# MT8365_DDR4X.net
KiCad netlist of a schematic drawn in Altium Designer
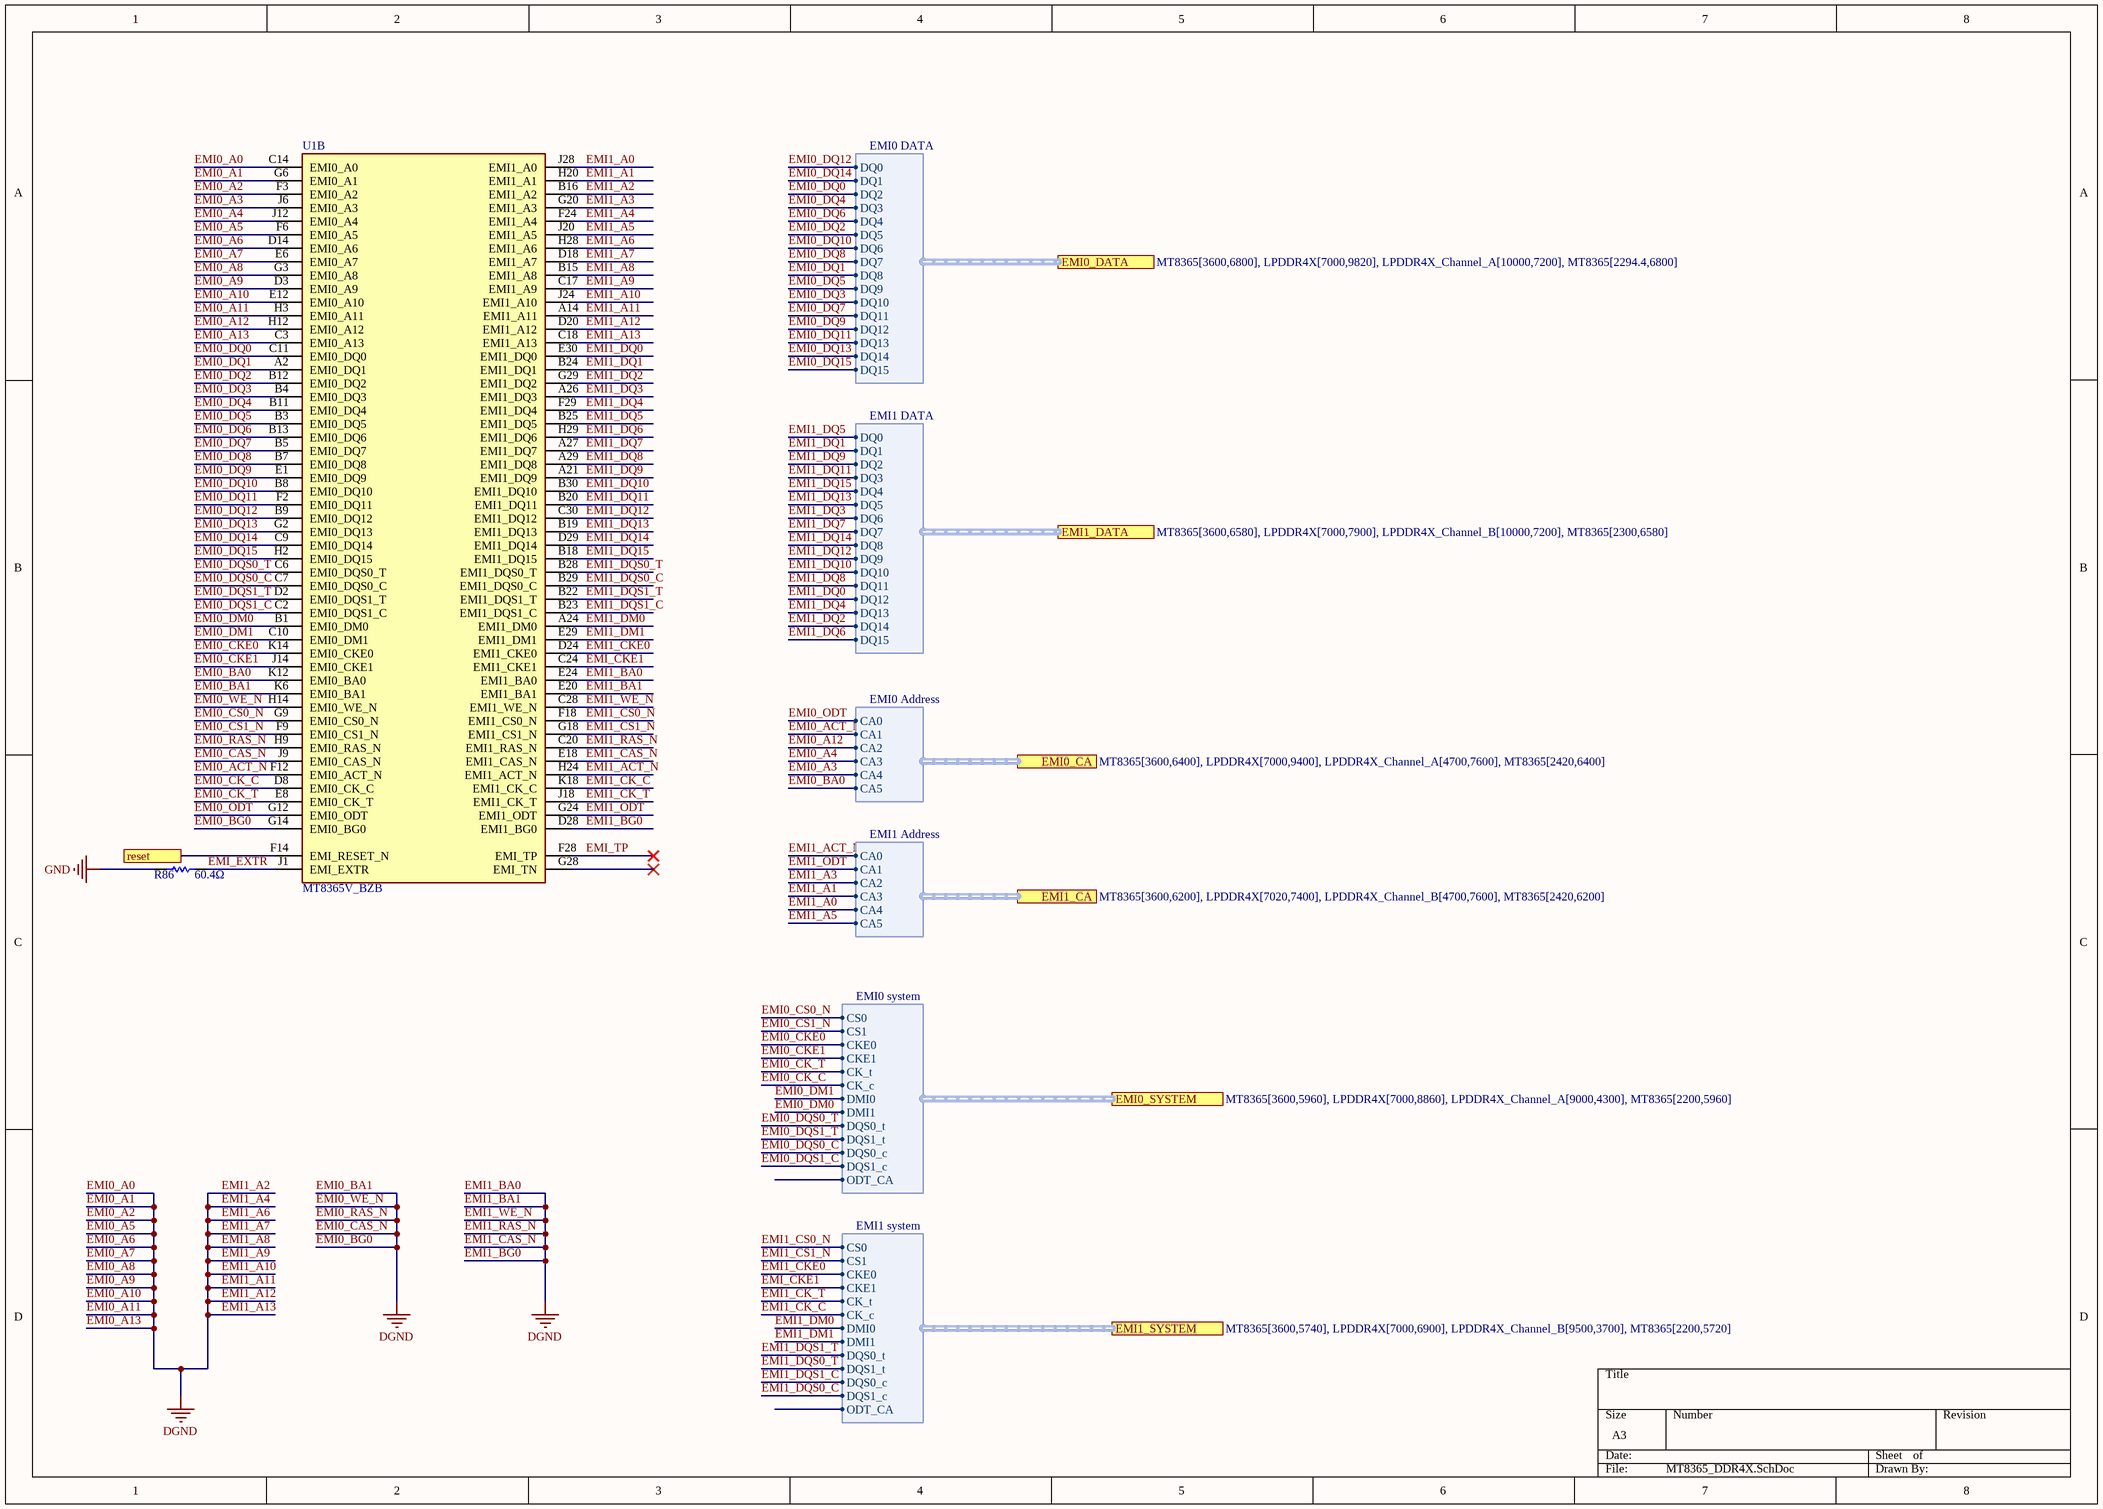
[diagram p0: MT8365_DDR4X.SchDoc]

(export (version "E")
  (design (tool "Eeschema 10.0.6"))
  (components
    (comp (ref "R86")
      (value "60.4Ω")
      (description "Resistor")
      (libsource (lib "Simulation Generic Components") (part "Resistor"))
    )
    (comp (ref "U1")
      (value "MT8365V_BZB")
      (footprint "BGA633C40P30X29_1220X1180X90")
      (description "Integrated Circuit")
      (fields
        (field (name "MANUFACTURER_PART_NUMBER") "MT8365V/BZB")
        (field (name "MOUSER PART NUMBER") "840-MT8365V/BZB")
      )
      (libsource (lib "kit") (part "MT8365V_BZB"))
    )
  )
  (nets
    (net (code "6") (name "/EMI0_A3") (class "Default")
      (node (ref "U1") (pin "J6") (pinfunction "EMI0_A3_J6") (pintype "passive"))
    )
    (net (code "7") (name "/EMI0_A4") (class "Default")
      (node (ref "U1") (pin "J12") (pinfunction "EMI0_A4_J12") (pintype "passive"))
    )
    (net (code "8") (name "/EMI0_A12") (class "Default")
      (node (ref "U1") (pin "H12") (pinfunction "EMI0_A12_H12") (pintype "passive"))
    )
    (net (code "9") (name "/EMI0_ACT_N") (class "Default")
      (node (ref "U1") (pin "F12") (pinfunction "EMI0_ACT_N_F12") (pintype "passive"))
    )
    (net (code "10") (name "/EMI0_BA0") (class "Default")
      (node (ref "U1") (pin "K12") (pinfunction "EMI0_BA0_K12") (pintype "passive"))
    )
    (net (code "11") (name "/EMI0_CKE0") (class "Default")
      (node (ref "U1") (pin "K14") (pinfunction "EMI0_CKE0_K14") (pintype "passive"))
    )
    (net (code "12") (name "/EMI0_CKE1") (class "Default")
      (node (ref "U1") (pin "J14") (pinfunction "EMI0_CKE1_J14") (pintype "passive"))
    )
    (net (code "13") (name "/EMI0_CK_C") (class "Default")
      (node (ref "U1") (pin "D8") (pinfunction "EMI0_CK_C_D8") (pintype "passive"))
    )
    (net (code "14") (name "/EMI0_CK_T") (class "Default")
      (node (ref "U1") (pin "E8") (pinfunction "EMI0_CK_T_E8") (pintype "passive"))
    )
    (net (code "15") (name "/EMI0_CS0_N") (class "Default")
      (node (ref "U1") (pin "G9") (pinfunction "EMI0_CS0_N_G9") (pintype "passive"))
    )
    (net (code "16") (name "/EMI0_CS1_N") (class "Default")
      (node (ref "U1") (pin "F9") (pinfunction "EMI0_CS1_N_F9") (pintype "passive"))
    )
    (net (code "17") (name "/EMI0_DM0") (class "Default")
      (node (ref "U1") (pin "B1") (pinfunction "EMI0_DM0_B1") (pintype "passive"))
    )
    (net (code "18") (name "/EMI0_DM1") (class "Default")
      (node (ref "U1") (pin "C10") (pinfunction "EMI0_DM1_C10") (pintype "passive"))
    )
    (net (code "19") (name "/EMI0_DQ0") (class "Default")
      (node (ref "U1") (pin "C11") (pinfunction "EMI0_DQ0_C11") (pintype "passive"))
    )
    (net (code "20") (name "/EMI0_DQ1") (class "Default")
      (node (ref "U1") (pin "A2") (pinfunction "EMI0_DQ1_A2") (pintype "passive"))
    )
    (net (code "21") (name "/EMI0_DQ2") (class "Default")
      (node (ref "U1") (pin "B12") (pinfunction "EMI0_DQ2_B12") (pintype "passive"))
    )
    (net (code "22") (name "/EMI0_DQ3") (class "Default")
      (node (ref "U1") (pin "B4") (pinfunction "EMI0_DQ3_B4") (pintype "passive"))
    )
    (net (code "23") (name "/EMI0_DQ4") (class "Default")
      (node (ref "U1") (pin "B11") (pinfunction "EMI0_DQ4_B11") (pintype "passive"))
    )
    (net (code "24") (name "/EMI0_DQ5") (class "Default")
      (node (ref "U1") (pin "B3") (pinfunction "EMI0_DQ5_B3") (pintype "passive"))
    )
    (net (code "25") (name "/EMI0_DQ6") (class "Default")
      (node (ref "U1") (pin "B13") (pinfunction "EMI0_DQ6_B13") (pintype "passive"))
    )
    (net (code "26") (name "/EMI0_DQ7") (class "Default")
      (node (ref "U1") (pin "B5") (pinfunction "EMI0_DQ7_B5") (pintype "passive"))
    )
    (net (code "27") (name "/EMI0_DQ8") (class "Default")
      (node (ref "U1") (pin "B7") (pinfunction "EMI0_DQ8_B7") (pintype "passive"))
    )
    (net (code "28") (name "/EMI0_DQ9") (class "Default")
      (node (ref "U1") (pin "E1") (pinfunction "EMI0_DQ9_E1") (pintype "passive"))
    )
    (net (code "29") (name "/EMI0_DQ10") (class "Default")
      (node (ref "U1") (pin "B8") (pinfunction "EMI0_DQ10_B8") (pintype "passive"))
    )
    (net (code "30") (name "/EMI0_DQ11") (class "Default")
      (node (ref "U1") (pin "F2") (pinfunction "EMI0_DQ11_F2") (pintype "passive"))
    )
    (net (code "31") (name "/EMI0_DQ12") (class "Default")
      (node (ref "U1") (pin "B9") (pinfunction "EMI0_DQ12_B9") (pintype "passive"))
    )
    (net (code "32") (name "/EMI0_DQ13") (class "Default")
      (node (ref "U1") (pin "G2") (pinfunction "EMI0_DQ13_G2") (pintype "passive"))
    )
    (net (code "33") (name "/EMI0_DQ14") (class "Default")
      (node (ref "U1") (pin "C9") (pinfunction "EMI0_DQ14_C9") (pintype "passive"))
    )
    (net (code "34") (name "/EMI0_DQ15") (class "Default")
      (node (ref "U1") (pin "H2") (pinfunction "EMI0_DQ15_H2") (pintype "passive"))
    )
    (net (code "35") (name "/EMI0_DQS0_C") (class "Default")
      (node (ref "U1") (pin "C7") (pinfunction "EMI0_DQS0_C_C7") (pintype "passive"))
    )
    (net (code "36") (name "/EMI0_DQS0_T") (class "Default")
      (node (ref "U1") (pin "C6") (pinfunction "EMI0_DQS0_T_C6") (pintype "passive"))
    )
    (net (code "37") (name "/EMI0_DQS1_C") (class "Default")
      (node (ref "U1") (pin "C2") (pinfunction "EMI0_DQS1_C_C2") (pintype "passive"))
    )
    (net (code "38") (name "/EMI0_DQS1_T") (class "Default")
      (node (ref "U1") (pin "D2") (pinfunction "EMI0_DQS1_T_D2") (pintype "passive"))
    )
    (net (code "39") (name "/EMI0_ODT") (class "Default")
      (node (ref "U1") (pin "G12") (pinfunction "EMI0_ODT_G12") (pintype "passive"))
    )
    (net (code "40") (name "/EMI1_A0") (class "Default")
      (node (ref "U1") (pin "J28") (pinfunction "EMI1_A0_J28") (pintype "passive"))
    )
    (net (code "41") (name "/EMI1_A1") (class "Default")
      (node (ref "U1") (pin "H20") (pinfunction "EMI1_A1_H20") (pintype "passive"))
    )
    (net (code "42") (name "/EMI1_A3") (class "Default")
      (node (ref "U1") (pin "G20") (pinfunction "EMI1_A3_G20") (pintype "passive"))
    )
    (net (code "43") (name "/EMI1_A5") (class "Default")
      (node (ref "U1") (pin "J20") (pinfunction "EMI1_A5_J20") (pintype "passive"))
    )
    (net (code "44") (name "/EMI1_ACT_N") (class "Default")
      (node (ref "U1") (pin "H24") (pinfunction "EMI1_ACT_N_H24") (pintype "passive"))
    )
    (net (code "45") (name "/EMI1_CKE0") (class "Default")
      (node (ref "U1") (pin "D24") (pinfunction "EMI1_CKE0_D24") (pintype "passive"))
    )
    (net (code "46") (name "/EMI1_CK_C") (class "Default")
      (node (ref "U1") (pin "K18") (pinfunction "EMI1_CK_C_K18") (pintype "passive"))
    )
    (net (code "47") (name "/EMI1_CK_T") (class "Default")
      (node (ref "U1") (pin "J18") (pinfunction "EMI1_CK_T_J18") (pintype "passive"))
    )
    (net (code "48") (name "/EMI1_CS0_N") (class "Default")
      (node (ref "U1") (pin "F18") (pinfunction "EMI1_CS0_N_F18") (pintype "passive"))
    )
    (net (code "49") (name "/EMI1_CS1_N") (class "Default")
      (node (ref "U1") (pin "G18") (pinfunction "EMI1_CS1_N_G18") (pintype "passive"))
    )
    (net (code "50") (name "/EMI1_DM0") (class "Default")
      (node (ref "U1") (pin "A24") (pinfunction "EMI1_DM0_A24") (pintype "passive"))
    )
    (net (code "51") (name "/EMI1_DM1") (class "Default")
      (node (ref "U1") (pin "E29") (pinfunction "EMI1_DM1_E29") (pintype "passive"))
    )
    (net (code "52") (name "/EMI1_DQ0") (class "Default")
      (node (ref "U1") (pin "E30") (pinfunction "EMI1_DQ0_E30") (pintype "passive"))
    )
    (net (code "53") (name "/EMI1_DQ1") (class "Default")
      (node (ref "U1") (pin "B24") (pinfunction "EMI1_DQ1_B24") (pintype "passive"))
    )
    (net (code "54") (name "/EMI1_DQ2") (class "Default")
      (node (ref "U1") (pin "G29") (pinfunction "EMI1_DQ2_G29") (pintype "passive"))
    )
    (net (code "55") (name "/EMI1_DQ3") (class "Default")
      (node (ref "U1") (pin "A26") (pinfunction "EMI1_DQ3_A26") (pintype "passive"))
    )
    (net (code "56") (name "/EMI1_DQ4") (class "Default")
      (node (ref "U1") (pin "F29") (pinfunction "EMI1_DQ4_F29") (pintype "passive"))
    )
    (net (code "57") (name "/EMI1_DQ5") (class "Default")
      (node (ref "U1") (pin "B25") (pinfunction "EMI1_DQ5_B25") (pintype "passive"))
    )
    (net (code "58") (name "/EMI1_DQ6") (class "Default")
      (node (ref "U1") (pin "H29") (pinfunction "EMI1_DQ6_H29") (pintype "passive"))
    )
    (net (code "59") (name "/EMI1_DQ7") (class "Default")
      (node (ref "U1") (pin "A27") (pinfunction "EMI1_DQ7_A27") (pintype "passive"))
    )
    (net (code "60") (name "/EMI1_DQ8") (class "Default")
      (node (ref "U1") (pin "A29") (pinfunction "EMI1_DQ8_A29") (pintype "passive"))
    )
    (net (code "61") (name "/EMI1_DQ9") (class "Default")
      (node (ref "U1") (pin "A21") (pinfunction "EMI1_DQ9_A21") (pintype "passive"))
    )
    (net (code "62") (name "/EMI1_DQ10") (class "Default")
      (node (ref "U1") (pin "B30") (pinfunction "EMI1_DQ10_B30") (pintype "passive"))
    )
    (net (code "63") (name "/EMI1_DQ11") (class "Default")
      (node (ref "U1") (pin "B20") (pinfunction "EMI1_DQ11_B20") (pintype "passive"))
    )
    (net (code "64") (name "/EMI1_DQ12") (class "Default")
      (node (ref "U1") (pin "C30") (pinfunction "EMI1_DQ12_C30") (pintype "passive"))
    )
    (net (code "65") (name "/EMI1_DQ13") (class "Default")
      (node (ref "U1") (pin "B19") (pinfunction "EMI1_DQ13_B19") (pintype "passive"))
    )
    (net (code "66") (name "/EMI1_DQ14") (class "Default")
      (node (ref "U1") (pin "D29") (pinfunction "EMI1_DQ14_D29") (pintype "passive"))
    )
    (net (code "67") (name "/EMI1_DQ15") (class "Default")
      (node (ref "U1") (pin "B18") (pinfunction "EMI1_DQ15_B18") (pintype "passive"))
    )
    (net (code "68") (name "/EMI1_DQS0_C") (class "Default")
      (node (ref "U1") (pin "B29") (pinfunction "EMI1_DQS0_C_B29") (pintype "passive"))
    )
    (net (code "69") (name "/EMI1_DQS0_T") (class "Default")
      (node (ref "U1") (pin "B28") (pinfunction "EMI1_DQS0_T_B28") (pintype "passive"))
    )
    (net (code "70") (name "/EMI1_DQS1_C") (class "Default")
      (node (ref "U1") (pin "B23") (pinfunction "EMI1_DQS1_C_B23") (pintype "passive"))
    )
    (net (code "71") (name "/EMI1_DQS1_T") (class "Default")
      (node (ref "U1") (pin "B22") (pinfunction "EMI1_DQS1_T_B22") (pintype "passive"))
    )
    (net (code "72") (name "/EMI1_ODT") (class "Default")
      (node (ref "U1") (pin "G24") (pinfunction "EMI1_ODT_G24") (pintype "passive"))
    )
    (net (code "73") (name "/EMI_CKE1") (class "Default")
      (node (ref "U1") (pin "C24") (pinfunction "EMI1_CKE1_C24") (pintype "passive"))
    )
    (net (code "74") (name "/EMI_EXTR") (class "Default")
      (node (ref "R86") (pin "2") (pinfunction "2_2") (pintype "passive"))
      (node (ref "U1") (pin "J1") (pinfunction "EMI_EXTR_J1") (pintype "passive"))
    )
    (net (code "75") (name "/EMI_TP") (class "Default")
      (node (ref "U1") (pin "F28") (pinfunction "EMI_TP_F28") (pintype "passive+no_connect"))
    )
    (net (code "76") (name "/reset") (class "Default")
      (node (ref "U1") (pin "F14") (pinfunction "EMI_RESET_N_F14") (pintype "passive"))
    )
    (net (code "83") (name "DGND") (class "Default")
      (node (ref "U1") (pin "A14") (pinfunction "EMI1_A11_A14") (pintype "passive"))
      (node (ref "U1") (pin "B15") (pinfunction "EMI1_A8_B15") (pintype "passive"))
      (node (ref "U1") (pin "B16") (pinfunction "EMI1_A2_B16") (pintype "passive"))
      (node (ref "U1") (pin "C14") (pinfunction "EMI0_A0_C14") (pintype "passive"))
      (node (ref "U1") (pin "C17") (pinfunction "EMI1_A9_C17") (pintype "passive"))
      (node (ref "U1") (pin "C18") (pinfunction "EMI1_A13_C18") (pintype "passive"))
      (node (ref "U1") (pin "C20") (pinfunction "EMI1_RAS_N_C20") (pintype "passive"))
      (node (ref "U1") (pin "C28") (pinfunction "EMI1_WE_N_C28") (pintype "passive"))
      (node (ref "U1") (pin "C3") (pinfunction "EMI0_A13_C3") (pintype "passive"))
      (node (ref "U1") (pin "D14") (pinfunction "EMI0_A6_D14") (pintype "passive"))
      (node (ref "U1") (pin "D18") (pinfunction "EMI1_A7_D18") (pintype "passive"))
      (node (ref "U1") (pin "D20") (pinfunction "EMI1_A12_D20") (pintype "passive"))
      (node (ref "U1") (pin "D28") (pinfunction "EMI1_BG0_D28") (pintype "passive"))
      (node (ref "U1") (pin "D3") (pinfunction "EMI0_A9_D3") (pintype "passive"))
      (node (ref "U1") (pin "E12") (pinfunction "EMI0_A10_E12") (pintype "passive"))
      (node (ref "U1") (pin "E18") (pinfunction "EMI1_CAS_N_E18") (pintype "passive"))
      (node (ref "U1") (pin "E20") (pinfunction "EMI1_BA1_E20") (pintype "passive"))
      (node (ref "U1") (pin "E24") (pinfunction "EMI1_BA0_E24") (pintype "passive"))
      (node (ref "U1") (pin "E6") (pinfunction "EMI0_A7_E6") (pintype "passive"))
      (node (ref "U1") (pin "F24") (pinfunction "EMI1_A4_F24") (pintype "passive"))
      (node (ref "U1") (pin "F3") (pinfunction "EMI0_A2_F3") (pintype "passive"))
      (node (ref "U1") (pin "F6") (pinfunction "EMI0_A5_F6") (pintype "passive"))
      (node (ref "U1") (pin "G14") (pinfunction "EMI0_BG0_G14") (pintype "passive"))
      (node (ref "U1") (pin "G3") (pinfunction "EMI0_A8_G3") (pintype "passive"))
      (node (ref "U1") (pin "G6") (pinfunction "EMI0_A1_G6") (pintype "passive"))
      (node (ref "U1") (pin "H14") (pinfunction "EMI0_WE_N_H14") (pintype "passive"))
      (node (ref "U1") (pin "H28") (pinfunction "EMI1_A6_H28") (pintype "passive"))
      (node (ref "U1") (pin "H3") (pinfunction "EMI0_A11_H3") (pintype "passive"))
      (node (ref "U1") (pin "H9") (pinfunction "EMI0_RAS_N_H9") (pintype "passive"))
      (node (ref "U1") (pin "J24") (pinfunction "EMI1_A10_J24") (pintype "passive"))
      (node (ref "U1") (pin "J9") (pinfunction "EMI0_CAS_N_J9") (pintype "passive"))
      (node (ref "U1") (pin "K6") (pinfunction "EMI0_BA1_K6") (pintype "passive"))
    )
    (net (code "84") (name "GND") (class "Default")
      (node (ref "R86") (pin "1") (pinfunction "1_1") (pintype "passive"))
    )
    (net (code "85") (name "unconnected-(U1B-EMI_TN-PadG28)") (class "Default")
      (node (ref "U1") (pin "G28") (pinfunction "EMI_TN_G28") (pintype "passive+no_connect"))
    )
  )
)
